# SD_card.net
KiCad netlist of a schematic drawn in Altium Designer
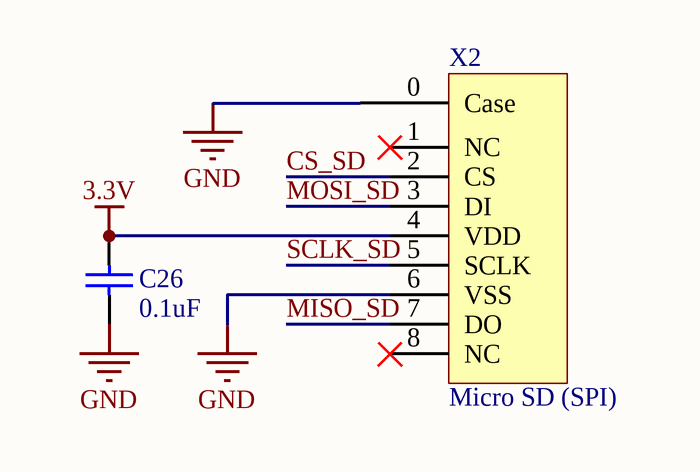
[diagram p0: SD_card.SchDoc]

(export (version "E")
  (design (tool "Eeschema 10.0.6"))
  (components
    (comp (ref "C26")
      (value "0.1uF")
      (footprint "Capacitors:C0603")
      (description "0.1uF ceramic capacitor")
      (fields (field (name "MANUFACTURER") "TDK Corporation") (field (name "TOLERANCE") "10%"))
      (libsource (lib "Capacitors") (part "CAP CER 0603 0.1uF 50V C0G 10%"))
    )
    (comp (ref "X2")
      (value "Micro SD (SPI)")
      (footprint "475710001")
      (description "microSD connector, Surface Mount, Right Angle")
      (fields (field (name "MANUFACTURER") "Molex") (field (name "PART_NUMBER") "47571-0001"))
      (libsource (lib "Other") (part "475710001"))
    )
  )
  (nets
    (net (code "1") (name "/CS_SD") (class "Default")
      (node (ref "X2") (pin "2") (pinfunction "CS_2") (pintype "passive"))
    )
    (net (code "2") (name "/MISO_SD") (class "Default")
      (node (ref "X2") (pin "7") (pinfunction "DO_7") (pintype "passive"))
    )
    (net (code "3") (name "/MOSI_SD") (class "Default")
      (node (ref "X2") (pin "3") (pinfunction "DI_3") (pintype "passive"))
    )
    (net (code "4") (name "/SCLK_SD") (class "Default")
      (node (ref "X2") (pin "5") (pinfunction "SCLK_5") (pintype "passive"))
    )
    (net (code "5") (name "3.3V") (class "Default")
      (node (ref "C26") (pin "2") (pinfunction "2_2") (pintype "passive"))
      (node (ref "X2") (pin "4") (pinfunction "VDD_4") (pintype "passive"))
    )
    (net (code "6") (name "GND") (class "Default")
      (node (ref "C26") (pin "1") (pinfunction "1_1") (pintype "passive"))
      (node (ref "X2") (pin "0") (pinfunction "Case_0") (pintype "passive"))
      (node (ref "X2") (pin "6") (pinfunction "VSS_6") (pintype "passive"))
    )
    (net (code "7") (name "unconnected-(X2-NC-Pad1)") (class "Default")
      (node (ref "X2") (pin "1") (pinfunction "NC_1") (pintype "passive+no_connect"))
    )
    (net (code "8") (name "unconnected-(X2-NC-Pad8)") (class "Default")
      (node (ref "X2") (pin "8") (pinfunction "NC_8") (pintype "passive+no_connect"))
    )
  )
)
